# HapticSleeveSchematic3_-_Copy.net
KiCad netlist of a schematic drawn in EAGLE
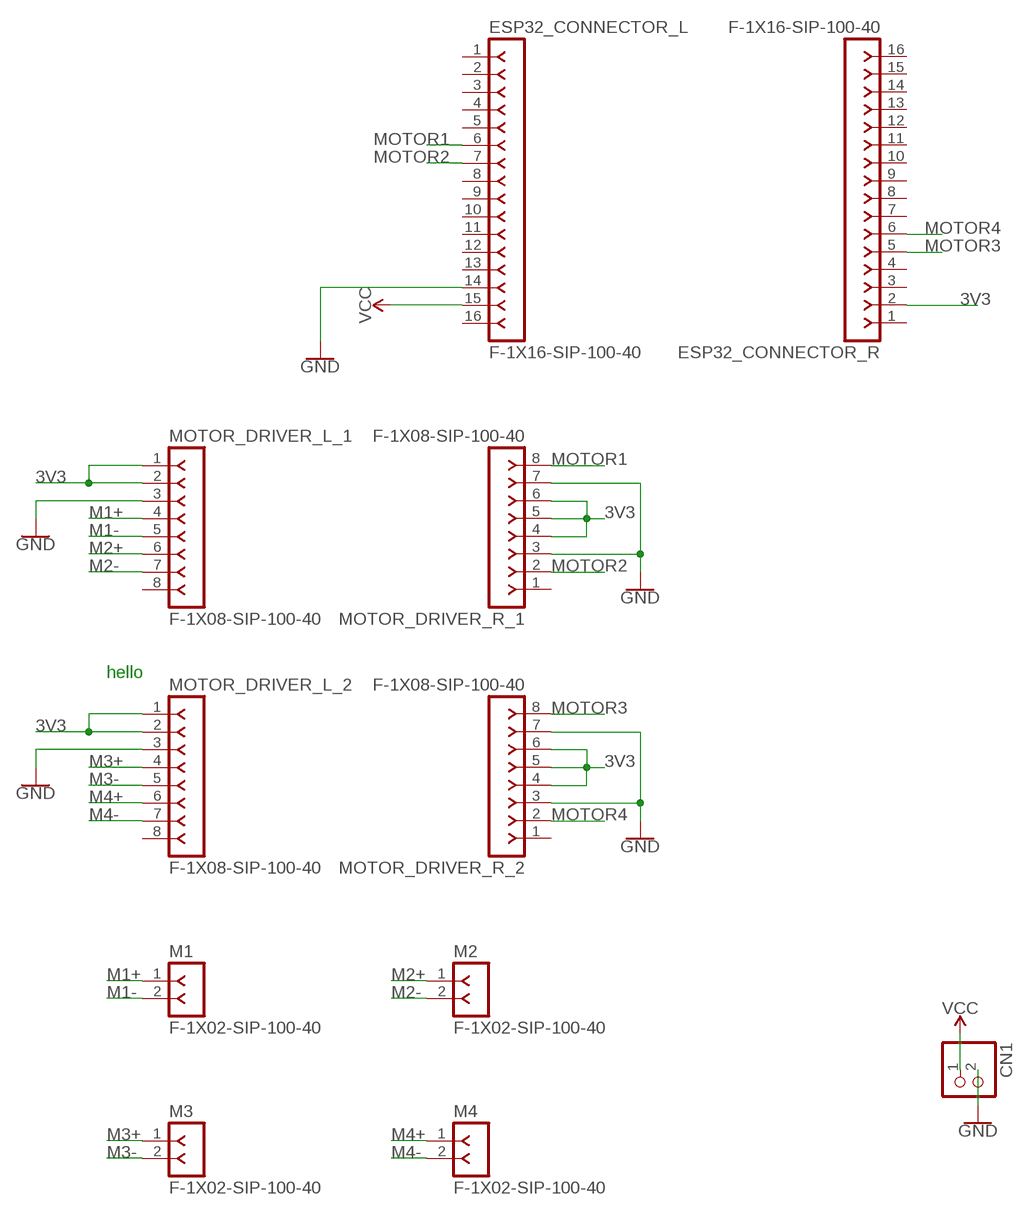
[diagram p0: schematic, sheet 1]

(export (version "E")
  (design (tool "Eeschema 10.0.6"))
  (components
    (comp (ref "CN1")
      (value "JST_2PIN-THM-RA")
      (footprint "eagle-import:JST-PH-2-THM-RA")
      (libsource (lib "eagle-import") (part "JST_2PIN-THM-RA"))
    )
    (comp (ref "ESP32_CONNECTOR_L")
      (value "F-1X16-SIP-100-40")
      (footprint "eagle-import:SIP-100-16-40")
      (libsource (lib "eagle-import") (part "F-1X16-SIP-100-40"))
    )
    (comp (ref "ESP32_CONNECTOR_R")
      (value "F-1X16-SIP-100-40")
      (footprint "eagle-import:SIP-100-16-40")
      (libsource (lib "eagle-import") (part "F-1X16-SIP-100-40"))
    )
    (comp (ref "M1")
      (value "F-1X02-SIP-100-40")
      (footprint "eagle-import:SIP-100-02-40")
      (libsource (lib "eagle-import") (part "F-1X02-SIP-100-40"))
    )
    (comp (ref "M2")
      (value "F-1X02-SIP-100-40")
      (footprint "eagle-import:SIP-100-02-40")
      (libsource (lib "eagle-import") (part "F-1X02-SIP-100-40"))
    )
    (comp (ref "M3")
      (value "F-1X02-SIP-100-40")
      (footprint "eagle-import:SIP-100-02-40")
      (libsource (lib "eagle-import") (part "F-1X02-SIP-100-40"))
    )
    (comp (ref "M4")
      (value "F-1X02-SIP-100-40")
      (footprint "eagle-import:SIP-100-02-40")
      (libsource (lib "eagle-import") (part "F-1X02-SIP-100-40"))
    )
    (comp (ref "MOTOR_DRIVER_L_1")
      (value "F-1X08-SIP-100-40")
      (footprint "eagle-import:SIP-100-08-40")
      (libsource (lib "eagle-import") (part "F-1X08-SIP-100-40"))
    )
    (comp (ref "MOTOR_DRIVER_L_2")
      (value "F-1X08-SIP-100-40")
      (footprint "eagle-import:SIP-100-08-40")
      (libsource (lib "eagle-import") (part "F-1X08-SIP-100-40"))
    )
    (comp (ref "MOTOR_DRIVER_R_1")
      (value "F-1X08-SIP-100-40")
      (footprint "eagle-import:SIP-100-08-40")
      (libsource (lib "eagle-import") (part "F-1X08-SIP-100-40"))
    )
    (comp (ref "MOTOR_DRIVER_R_2")
      (value "F-1X08-SIP-100-40")
      (footprint "eagle-import:SIP-100-08-40")
      (libsource (lib "eagle-import") (part "F-1X08-SIP-100-40"))
    )
  )
  (nets
    (net (code "1") (name "/3V3") (class "Default")
      (node (ref "ESP32_CONNECTOR_R") (pin "2") (pinfunction "2_2") (pintype "passive"))
      (node (ref "MOTOR_DRIVER_L_1") (pin "1") (pinfunction "1_1") (pintype "passive"))
      (node (ref "MOTOR_DRIVER_L_1") (pin "2") (pinfunction "2_2") (pintype "passive"))
      (node (ref "MOTOR_DRIVER_L_2") (pin "1") (pinfunction "1_1") (pintype "passive"))
      (node (ref "MOTOR_DRIVER_L_2") (pin "2") (pinfunction "2_2") (pintype "passive"))
      (node (ref "MOTOR_DRIVER_R_1") (pin "4") (pinfunction "4_4") (pintype "passive"))
      (node (ref "MOTOR_DRIVER_R_1") (pin "5") (pinfunction "5_5") (pintype "passive"))
      (node (ref "MOTOR_DRIVER_R_1") (pin "6") (pinfunction "6_6") (pintype "passive"))
      (node (ref "MOTOR_DRIVER_R_2") (pin "4") (pinfunction "4_4") (pintype "passive"))
      (node (ref "MOTOR_DRIVER_R_2") (pin "5") (pinfunction "5_5") (pintype "passive"))
      (node (ref "MOTOR_DRIVER_R_2") (pin "6") (pinfunction "6_6") (pintype "passive"))
    )
    (net (code "2") (name "/M1+") (class "Default")
      (node (ref "M1") (pin "1") (pinfunction "1_1") (pintype "passive"))
      (node (ref "MOTOR_DRIVER_L_1") (pin "4") (pinfunction "4_4") (pintype "passive"))
    )
    (net (code "3") (name "/M1-") (class "Default")
      (node (ref "M1") (pin "2") (pinfunction "2_2") (pintype "passive"))
      (node (ref "MOTOR_DRIVER_L_1") (pin "5") (pinfunction "5_5") (pintype "passive"))
    )
    (net (code "4") (name "/M2+") (class "Default")
      (node (ref "M2") (pin "1") (pinfunction "1_1") (pintype "passive"))
      (node (ref "MOTOR_DRIVER_L_1") (pin "6") (pinfunction "6_6") (pintype "passive"))
    )
    (net (code "5") (name "/M2-") (class "Default")
      (node (ref "M2") (pin "2") (pinfunction "2_2") (pintype "passive"))
      (node (ref "MOTOR_DRIVER_L_1") (pin "7") (pinfunction "7_7") (pintype "passive"))
    )
    (net (code "6") (name "/M3+") (class "Default")
      (node (ref "M3") (pin "1") (pinfunction "1_1") (pintype "passive"))
      (node (ref "MOTOR_DRIVER_L_2") (pin "4") (pinfunction "4_4") (pintype "passive"))
    )
    (net (code "7") (name "/M3-") (class "Default")
      (node (ref "M3") (pin "2") (pinfunction "2_2") (pintype "passive"))
      (node (ref "MOTOR_DRIVER_L_2") (pin "5") (pinfunction "5_5") (pintype "passive"))
    )
    (net (code "8") (name "/M4+") (class "Default")
      (node (ref "M4") (pin "1") (pinfunction "1_1") (pintype "passive"))
      (node (ref "MOTOR_DRIVER_L_2") (pin "6") (pinfunction "6_6") (pintype "passive"))
    )
    (net (code "9") (name "/M4-") (class "Default")
      (node (ref "M4") (pin "2") (pinfunction "2_2") (pintype "passive"))
      (node (ref "MOTOR_DRIVER_L_2") (pin "7") (pinfunction "7_7") (pintype "passive"))
    )
    (net (code "10") (name "/MOTOR1") (class "Default")
      (node (ref "ESP32_CONNECTOR_L") (pin "6") (pinfunction "6_6") (pintype "passive"))
      (node (ref "MOTOR_DRIVER_R_1") (pin "8") (pinfunction "8_8") (pintype "passive"))
    )
    (net (code "11") (name "/MOTOR2") (class "Default")
      (node (ref "ESP32_CONNECTOR_L") (pin "7") (pinfunction "7_7") (pintype "passive"))
      (node (ref "MOTOR_DRIVER_R_1") (pin "2") (pinfunction "2_2") (pintype "passive"))
    )
    (net (code "12") (name "/MOTOR3") (class "Default")
      (node (ref "ESP32_CONNECTOR_R") (pin "5") (pinfunction "5_5") (pintype "passive"))
      (node (ref "MOTOR_DRIVER_R_2") (pin "8") (pinfunction "8_8") (pintype "passive"))
    )
    (net (code "13") (name "/MOTOR4") (class "Default")
      (node (ref "ESP32_CONNECTOR_R") (pin "6") (pinfunction "6_6") (pintype "passive"))
      (node (ref "MOTOR_DRIVER_R_2") (pin "2") (pinfunction "2_2") (pintype "passive"))
    )
    (net (code "14") (name "GND") (class "Default")
      (node (ref "CN1") (pin "2") (pinfunction "1_2") (pintype "passive"))
      (node (ref "ESP32_CONNECTOR_L") (pin "14") (pinfunction "14_14") (pintype "passive"))
      (node (ref "MOTOR_DRIVER_L_1") (pin "3") (pinfunction "3_3") (pintype "passive"))
      (node (ref "MOTOR_DRIVER_L_2") (pin "3") (pinfunction "3_3") (pintype "passive"))
      (node (ref "MOTOR_DRIVER_R_1") (pin "3") (pinfunction "3_3") (pintype "passive"))
      (node (ref "MOTOR_DRIVER_R_1") (pin "7") (pinfunction "7_7") (pintype "passive"))
      (node (ref "MOTOR_DRIVER_R_2") (pin "3") (pinfunction "3_3") (pintype "passive"))
      (node (ref "MOTOR_DRIVER_R_2") (pin "7") (pinfunction "7_7") (pintype "passive"))
    )
    (net (code "15") (name "VCC") (class "Default")
      (node (ref "CN1") (pin "1") (pinfunction "2_1") (pintype "passive"))
      (node (ref "ESP32_CONNECTOR_L") (pin "15") (pinfunction "15_15") (pintype "passive"))
    )
    (net (code "16") (name "unconnected-(ESP32_CONNECTOR_L-Pad1)") (class "Default")
      (node (ref "ESP32_CONNECTOR_L") (pin "1") (pinfunction "1_1") (pintype "passive"))
    )
    (net (code "17") (name "unconnected-(ESP32_CONNECTOR_L-Pad2)") (class "Default")
      (node (ref "ESP32_CONNECTOR_L") (pin "2") (pinfunction "2_2") (pintype "passive"))
    )
    (net (code "18") (name "unconnected-(ESP32_CONNECTOR_L-Pad3)") (class "Default")
      (node (ref "ESP32_CONNECTOR_L") (pin "3") (pinfunction "3_3") (pintype "passive"))
    )
    (net (code "19") (name "unconnected-(ESP32_CONNECTOR_L-Pad4)") (class "Default")
      (node (ref "ESP32_CONNECTOR_L") (pin "4") (pinfunction "4_4") (pintype "passive"))
    )
    (net (code "20") (name "unconnected-(ESP32_CONNECTOR_L-Pad5)") (class "Default")
      (node (ref "ESP32_CONNECTOR_L") (pin "5") (pinfunction "5_5") (pintype "passive"))
    )
    (net (code "21") (name "unconnected-(ESP32_CONNECTOR_L-Pad8)") (class "Default")
      (node (ref "ESP32_CONNECTOR_L") (pin "8") (pinfunction "8_8") (pintype "passive"))
    )
    (net (code "22") (name "unconnected-(ESP32_CONNECTOR_L-Pad9)") (class "Default")
      (node (ref "ESP32_CONNECTOR_L") (pin "9") (pinfunction "9_9") (pintype "passive"))
    )
    (net (code "23") (name "unconnected-(ESP32_CONNECTOR_L-Pad10)") (class "Default")
      (node (ref "ESP32_CONNECTOR_L") (pin "10") (pinfunction "10_10") (pintype "passive"))
    )
    (net (code "24") (name "unconnected-(ESP32_CONNECTOR_L-Pad11)") (class "Default")
      (node (ref "ESP32_CONNECTOR_L") (pin "11") (pinfunction "11_11") (pintype "passive"))
    )
    (net (code "25") (name "unconnected-(ESP32_CONNECTOR_L-Pad12)") (class "Default")
      (node (ref "ESP32_CONNECTOR_L") (pin "12") (pinfunction "12_12") (pintype "passive"))
    )
    (net (code "26") (name "unconnected-(ESP32_CONNECTOR_L-Pad13)") (class "Default")
      (node (ref "ESP32_CONNECTOR_L") (pin "13") (pinfunction "13_13") (pintype "passive"))
    )
    (net (code "27") (name "unconnected-(ESP32_CONNECTOR_L-Pad16)") (class "Default")
      (node (ref "ESP32_CONNECTOR_L") (pin "16") (pinfunction "16_16") (pintype "passive"))
    )
    (net (code "28") (name "unconnected-(ESP32_CONNECTOR_R-Pad1)") (class "Default")
      (node (ref "ESP32_CONNECTOR_R") (pin "1") (pinfunction "1_1") (pintype "passive"))
    )
    (net (code "29") (name "unconnected-(ESP32_CONNECTOR_R-Pad3)") (class "Default")
      (node (ref "ESP32_CONNECTOR_R") (pin "3") (pinfunction "3_3") (pintype "passive"))
    )
    (net (code "30") (name "unconnected-(ESP32_CONNECTOR_R-Pad4)") (class "Default")
      (node (ref "ESP32_CONNECTOR_R") (pin "4") (pinfunction "4_4") (pintype "passive"))
    )
    (net (code "31") (name "unconnected-(ESP32_CONNECTOR_R-Pad7)") (class "Default")
      (node (ref "ESP32_CONNECTOR_R") (pin "7") (pinfunction "7_7") (pintype "passive"))
    )
    (net (code "32") (name "unconnected-(ESP32_CONNECTOR_R-Pad8)") (class "Default")
      (node (ref "ESP32_CONNECTOR_R") (pin "8") (pinfunction "8_8") (pintype "passive"))
    )
    (net (code "33") (name "unconnected-(ESP32_CONNECTOR_R-Pad9)") (class "Default")
      (node (ref "ESP32_CONNECTOR_R") (pin "9") (pinfunction "9_9") (pintype "passive"))
    )
    (net (code "34") (name "unconnected-(ESP32_CONNECTOR_R-Pad10)") (class "Default")
      (node (ref "ESP32_CONNECTOR_R") (pin "10") (pinfunction "10_10") (pintype "passive"))
    )
    (net (code "35") (name "unconnected-(ESP32_CONNECTOR_R-Pad11)") (class "Default")
      (node (ref "ESP32_CONNECTOR_R") (pin "11") (pinfunction "11_11") (pintype "passive"))
    )
    (net (code "36") (name "unconnected-(ESP32_CONNECTOR_R-Pad12)") (class "Default")
      (node (ref "ESP32_CONNECTOR_R") (pin "12") (pinfunction "12_12") (pintype "passive"))
    )
    (net (code "37") (name "unconnected-(ESP32_CONNECTOR_R-Pad13)") (class "Default")
      (node (ref "ESP32_CONNECTOR_R") (pin "13") (pinfunction "13_13") (pintype "passive"))
    )
    (net (code "38") (name "unconnected-(ESP32_CONNECTOR_R-Pad14)") (class "Default")
      (node (ref "ESP32_CONNECTOR_R") (pin "14") (pinfunction "14_14") (pintype "passive"))
    )
    (net (code "39") (name "unconnected-(ESP32_CONNECTOR_R-Pad15)") (class "Default")
      (node (ref "ESP32_CONNECTOR_R") (pin "15") (pinfunction "15_15") (pintype "passive"))
    )
    (net (code "40") (name "unconnected-(ESP32_CONNECTOR_R-Pad16)") (class "Default")
      (node (ref "ESP32_CONNECTOR_R") (pin "16") (pinfunction "16_16") (pintype "passive"))
    )
    (net (code "41") (name "unconnected-(MOTOR_DRIVER_L_1-Pad8)") (class "Default")
      (node (ref "MOTOR_DRIVER_L_1") (pin "8") (pinfunction "8_8") (pintype "passive"))
    )
    (net (code "42") (name "unconnected-(MOTOR_DRIVER_L_2-Pad8)") (class "Default")
      (node (ref "MOTOR_DRIVER_L_2") (pin "8") (pinfunction "8_8") (pintype "passive"))
    )
    (net (code "43") (name "unconnected-(MOTOR_DRIVER_R_1-Pad1)") (class "Default")
      (node (ref "MOTOR_DRIVER_R_1") (pin "1") (pinfunction "1_1") (pintype "passive"))
    )
    (net (code "44") (name "unconnected-(MOTOR_DRIVER_R_2-Pad1)") (class "Default")
      (node (ref "MOTOR_DRIVER_R_2") (pin "1") (pinfunction "1_1") (pintype "passive"))
    )
  )
)
